# Amplifier.net
KiCad netlist of a schematic drawn in Altium Designer
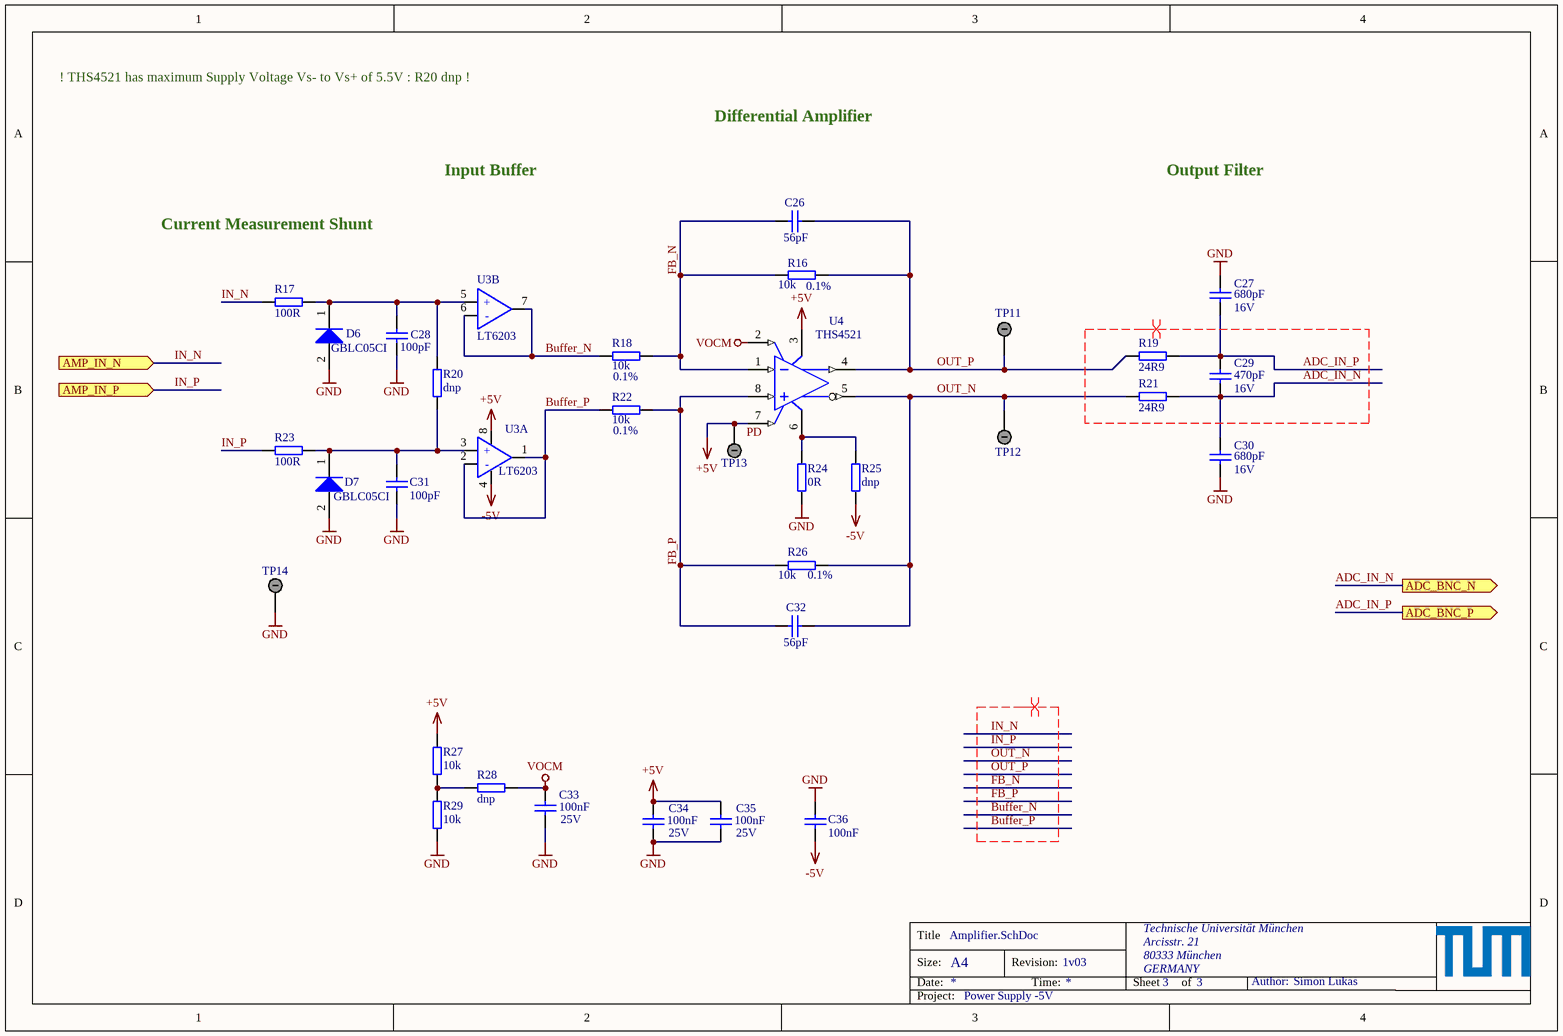
[diagram p0: Amplifier.SchDoc]

(export (version "E")
  (design (tool "Eeschema 10.0.6"))
  (components
    (comp (ref "C26")
      (value "56pF")
      (footprint "CAPC1608X07N")
      (fields
        (field (name "MF") "Vishay")
        (field (name "MPN") "VJ0603A560JXACW1BC")
        (field (name "VOLTAGE") "50V")
      )
      (libsource (lib "neg5V") (part "Cap_0603"))
    )
    (comp (ref "C27")
      (value "680pF")
      (footprint "CAPC1608X07N")
      (fields
        (field (name "MF") "Vishay")
        (field (name "MPN") "VJ0603A681GXJCW1BC")
        (field (name "VOLTAGE") "16V")
      )
      (libsource (lib "neg5V") (part "Cap_0603"))
    )
    (comp (ref "C28")
      (value "100pF")
      (footprint "CAPC1608X07N")
      (fields
        (field (name "MF") "Würth Elektronik")
        (field (name "MPN") "885012006057")
        (field (name "VOLTAGE") "50V")
      )
      (libsource (lib "neg5V") (part "Cap_0603"))
    )
    (comp (ref "C29")
      (value "470pF")
      (footprint "CAPC1608X07N")
      (fields
        (field (name "MF") "Vishay")
        (field (name "MPN") "VJ0603A471JXJCW1BC")
        (field (name "VOLTAGE") "16V")
      )
      (libsource (lib "neg5V") (part "Cap_0603"))
    )
    (comp (ref "C30")
      (value "680pF")
      (footprint "CAPC1608X07N")
      (fields
        (field (name "MF") "Vishay")
        (field (name "MPN") "VJ0603A681GXJCW1BC")
        (field (name "VOLTAGE") "16V")
      )
      (libsource (lib "neg5V") (part "Cap_0603"))
    )
    (comp (ref "C31")
      (value "100pF")
      (footprint "CAPC1608X07N")
      (fields
        (field (name "MF") "Würth Elektronik")
        (field (name "MPN") "885012006057")
        (field (name "VOLTAGE") "50V")
      )
      (libsource (lib "neg5V") (part "Cap_0603"))
    )
    (comp (ref "C32")
      (value "56pF")
      (footprint "CAPC1608X07N")
      (fields
        (field (name "MF") "Vishay")
        (field (name "MPN") "VJ0603A560JXACW1BC")
        (field (name "VOLTAGE") "50V")
      )
      (libsource (lib "neg5V") (part "Cap_0603"))
    )
    (comp (ref "C33")
      (value "100nF")
      (footprint "CAPC1608X07N")
      (fields
        (field (name "MF") "Würth Elektronik")
        (field (name "MPN") "885012206071")
        (field (name "VOLTAGE") "25V")
      )
      (libsource (lib "neg5V") (part "Cap_0603"))
    )
    (comp (ref "C34")
      (value "100nF")
      (footprint "CAPC1608X07N")
      (fields
        (field (name "MF") "Würth Elektronik")
        (field (name "MPN") "885012206071")
        (field (name "VOLTAGE") "25V")
      )
      (libsource (lib "neg5V") (part "Cap_0603"))
    )
    (comp (ref "C35")
      (value "100nF")
      (footprint "CAPC1608X07N")
      (fields
        (field (name "MF") "Würth Elektronik")
        (field (name "MPN") "885012206071")
        (field (name "VOLTAGE") "25V")
      )
      (libsource (lib "neg5V") (part "Cap_0603"))
    )
    (comp (ref "C36")
      (value "100nF")
      (footprint "CAPC1608X07N")
      (fields
        (field (name "MF") "Würth Elektronik")
        (field (name "MPN") "885012206071")
        (field (name "VOLTAGE") "25V")
      )
      (libsource (lib "neg5V") (part "Cap_0603"))
    )
    (comp (ref "D6")
      (value "GBLC05CI")
      (footprint "SOD-323_SuppressorDiode")
      (description "Ultra Low Capacitance TVS Array")
      (fields (field (name "MF") "ProTek Devices") (field (name "MPN") "GBLC05CI-LF-T7"))
      (libsource (lib "neg5V") (part "GBLCxx"))
    )
    (comp (ref "D7")
      (value "GBLC05CI")
      (footprint "SOD-323_SuppressorDiode")
      (description "Ultra Low Capacitance TVS Array")
      (fields (field (name "MF") "ProTek Devices") (field (name "MPN") "GBLC05CI-LF-T7"))
      (libsource (lib "neg5V") (part "GBLCxx"))
    )
    (comp (ref "R16")
      (value "10k")
      (footprint "RESC1608X06N")
      (fields
        (field (name "MF") "Yageo")
        (field (name "MPN") "RE0603BRE0710KL")
        (field (name "TOLERANCE") "0.1%")
      )
      (libsource (lib "neg5V") (part "R_0603"))
    )
    (comp (ref "R17")
      (value "100R")
      (footprint "RESC1608X06N")
      (fields
        (field (name "MF") "Yageo")
        (field (name "MPN") "AC0603FR-13100RL")
        (field (name "TOLERANCE") "1%")
      )
      (libsource (lib "neg5V") (part "R_0603"))
    )
    (comp (ref "R18")
      (value "10k")
      (footprint "RESC1608X06N")
      (fields
        (field (name "MF") "Yageo")
        (field (name "MPN") "RE0603BRE0710KL")
        (field (name "TOLERANCE") "0.1%")
      )
      (libsource (lib "neg5V") (part "R_0603"))
    )
    (comp (ref "R19")
      (value "24R9")
      (footprint "RESC1608X06N")
      (fields (field (name "MF") "Yageo") (field (name "MPN") "RC0603FR-1324R9L"))
      (libsource (lib "neg5V") (part "R_0603"))
    )
    (comp (ref "R20")
      (value "dnp")
      (footprint "RESC3216X65N")
      (description "WID SMD 1M 5% 0,25W")
      (fields (field (name "TOLERANCE") "5%") (field (name "MF") "ARCOL/Ohmite"))
      (libsource (lib "neg5V") (part "R_1206"))
    )
    (comp (ref "R21")
      (value "24R9")
      (footprint "RESC1608X06N")
      (fields (field (name "MF") "Yageo") (field (name "MPN") "RC0603FR-1324R9L"))
      (libsource (lib "neg5V") (part "R_0603"))
    )
    (comp (ref "R22")
      (value "10k")
      (footprint "RESC1608X06N")
      (fields
        (field (name "MF") "Yageo")
        (field (name "MPN") "RE0603BRE0710KL")
        (field (name "TOLERANCE") "0.1%")
      )
      (libsource (lib "neg5V") (part "R_0603"))
    )
    (comp (ref "R23")
      (value "100R")
      (footprint "RESC1608X06N")
      (fields
        (field (name "MF") "Yageo")
        (field (name "MPN") "AC0603FR-13100RL")
        (field (name "TOLERANCE") "1%")
      )
      (libsource (lib "neg5V") (part "R_0603"))
    )
    (comp (ref "R24")
      (value "0R")
      (footprint "RESC1608X06N")
      (fields (field (name "MF") "Vishay / Dale") (field (name "MPN") "CRCW06030000Z0EBC"))
      (libsource (lib "neg5V") (part "R_0603"))
    )
    (comp (ref "R25") (value "dnp") (footprint "RESC1608X06N") (libsource (lib "neg5V") (part "R_0603")))
    (comp (ref "R26")
      (value "10k")
      (footprint "RESC1608X06N")
      (fields
        (field (name "MF") "Yageo")
        (field (name "MPN") "RE0603BRE0710KL")
        (field (name "TOLERANCE") "0.1%")
      )
      (libsource (lib "neg5V") (part "R_0603"))
    )
    (comp (ref "R27")
      (value "10k")
      (footprint "RESC1608X06N")
      (fields (field (name "MF") "Vishay / Dale") (field (name "MPN") "CRCW060310K0FKEAC"))
      (libsource (lib "neg5V") (part "R_0603"))
    )
    (comp (ref "R28") (value "dnp") (footprint "RESC1608X06N") (libsource (lib "neg5V") (part "R_0603")))
    (comp (ref "R29")
      (value "10k")
      (footprint "RESC1608X06N")
      (fields (field (name "MF") "Vishay / Dale") (field (name "MPN") "CRCW060310K0FKEAC"))
      (libsource (lib "neg5V") (part "R_0603"))
    )
    (comp (ref "TP11")
      (value "AMP+")
      (footprint "TP_5006")
      (description "Test Point;  Compact;  THM;  PC;  .350 L;  .125 OD;  Heat Resistant Nylon 46;  Black")
      (fields
        (field (name "MANUFACTURER") "Keystone Electronics")
        (field (name "MANUFACTURER PART NUMBER") "5006")
      )
      (libsource (lib "neg5V") (part "5006"))
    )
    (comp (ref "TP12")
      (value "AMP-")
      (footprint "TP_5006")
      (description "Test Point;  Compact;  THM;  PC;  .350 L;  .125 OD;  Heat Resistant Nylon 46;  Black")
      (fields
        (field (name "MANUFACTURER") "Keystone Electronics")
        (field (name "MANUFACTURER PART NUMBER") "5006")
      )
      (libsource (lib "neg5V") (part "5006"))
    )
    (comp (ref "TP13")
      (value "PD")
      (footprint "TP_5006")
      (description "Test Point;  Compact;  THM;  PC;  .350 L;  .125 OD;  Heat Resistant Nylon 46;  Black")
      (fields
        (field (name "MANUFACTURER") "Keystone Electronics")
        (field (name "MANUFACTURER PART NUMBER") "5006")
      )
      (libsource (lib "neg5V") (part "5006"))
    )
    (comp (ref "TP14")
      (value "GND")
      (footprint "TP_5006")
      (description "Test Point;  Compact;  THM;  PC;  .350 L;  .125 OD;  Heat Resistant Nylon 46;  Black")
      (fields
        (field (name "MANUFACTURER") "Keystone Electronics")
        (field (name "MANUFACTURER PART NUMBER") "5006")
      )
      (libsource (lib "neg5V") (part "5006"))
    )
    (comp (ref "U3")
      (value "LT6203")
      (footprint "MSOP8_3x3-8N")
      (description "2 Ch Low Noise, Low Power OpAmp")
      (fields
        (field (name "MF") "Analog Devices / Linear Technology")
        (field (name "MPN") "LT6203CMS8#PBF")
        (field (name "CREATED") "Kreppel_20190830")
      )
      (libsource (lib "neg5V") (part "LT6203_MSOP8"))
    )
    (comp (ref "U4")
      (value "THS4521")
      (footprint "DGK0008A_N")
      (description "IC AMP RRO NEG OUT VLP 8VSSOP (Single Channel fully differential Amplifier)")
      (fields
        (field (name "MANUFACTURER") "Texas Instruments")
        (field (name "MANUFACTURER PART NUMBER") "THS4521IDGKR")
      )
      (libsource (lib "neg5V") (part "THS4521IDGKR"))
    )
  )
  (nets
    (net (code "1") (name "+5V") (class "Default")
      (node (ref "C34") (pin "1") (pinfunction "1_1") (pintype "passive"))
      (node (ref "C35") (pin "1") (pinfunction "1_1") (pintype "passive"))
      (node (ref "R27") (pin "1") (pintype "passive"))
      (node (ref "TP13") (pin "1") (pintype "passive"))
      (node (ref "U3") (pin "8") (pintype "passive"))
      (node (ref "U4") (pin "3") (pinfunction "VS+_3") (pintype "power_in"))
      (node (ref "U4") (pin "7") (pinfunction "~{PD}_7") (pintype "input"))
    )
    (net (code "2") (name "-5V") (class "Default")
      (node (ref "C36") (pin "2") (pinfunction "2_2") (pintype "passive"))
      (node (ref "R25") (pin "1") (pintype "passive"))
      (node (ref "U3") (pin "4") (pintype "passive"))
    )
    (net (code "3") (name "/ADC_IN_N") (class "Default")
      (node (ref "C29") (pin "2") (pinfunction "2_2") (pintype "passive"))
      (node (ref "C30") (pin "1") (pinfunction "1_1") (pintype "passive"))
      (node (ref "R21") (pin "2") (pintype "passive"))
    )
    (net (code "4") (name "/ADC_IN_P") (class "Default")
      (node (ref "C27") (pin "2") (pinfunction "2_2") (pintype "passive"))
      (node (ref "C29") (pin "1") (pinfunction "1_1") (pintype "passive"))
      (node (ref "R19") (pin "2") (pintype "passive"))
    )
    (net (code "5") (name "/Buffer_N") (class "Default")
      (node (ref "R18") (pin "1") (pintype "passive"))
      (node (ref "U3") (pin "6") (pinfunction "-_6") (pintype "passive"))
      (node (ref "U3") (pin "7") (pintype "passive"))
    )
    (net (code "6") (name "/Buffer_P") (class "Default")
      (node (ref "R22") (pin "1") (pintype "passive"))
      (node (ref "U3") (pin "1") (pintype "passive"))
      (node (ref "U3") (pin "2") (pinfunction "-_2") (pintype "passive"))
    )
    (net (code "7") (name "/FB_N") (class "Default")
      (node (ref "C26") (pin "1") (pinfunction "1_1") (pintype "passive"))
      (node (ref "R16") (pin "1") (pintype "passive"))
      (node (ref "R18") (pin "2") (pintype "passive"))
      (node (ref "U4") (pin "1") (pinfunction "VIN-_1") (pintype "input"))
    )
    (net (code "8") (name "/FB_P") (class "Default")
      (node (ref "C32") (pin "1") (pinfunction "1_1") (pintype "passive"))
      (node (ref "R22") (pin "2") (pintype "passive"))
      (node (ref "R26") (pin "1") (pintype "passive"))
      (node (ref "U4") (pin "8") (pinfunction "VIN+_8") (pintype "input"))
    )
    (net (code "9") (name "/IN_N") (class "Default") (node (ref "R17") (pin "1") (pintype "passive")))
    (net (code "10") (name "/IN_P") (class "Default") (node (ref "R23") (pin "1") (pintype "passive")))
    (net (code "11") (name "/OUT_N") (class "Default")
      (node (ref "C32") (pin "2") (pinfunction "2_2") (pintype "passive"))
      (node (ref "R21") (pin "1") (pintype "passive"))
      (node (ref "R26") (pin "2") (pintype "passive"))
      (node (ref "TP12") (pin "1") (pintype "passive"))
      (node (ref "U4") (pin "5") (pinfunction "VOUT-_5") (pintype "output"))
    )
    (net (code "12") (name "/OUT_P") (class "Default")
      (node (ref "C26") (pin "2") (pinfunction "2_2") (pintype "passive"))
      (node (ref "R16") (pin "2") (pintype "passive"))
      (node (ref "R19") (pin "1") (pintype "passive"))
      (node (ref "TP11") (pin "1") (pintype "passive"))
      (node (ref "U4") (pin "4") (pinfunction "VOUT+_4") (pintype "output"))
    )
    (net (code "14") (name "GND") (class "Default")
      (node (ref "C27") (pin "1") (pinfunction "1_1") (pintype "passive"))
      (node (ref "C28") (pin "2") (pinfunction "2_2") (pintype "passive"))
      (node (ref "C30") (pin "2") (pinfunction "2_2") (pintype "passive"))
      (node (ref "C31") (pin "2") (pinfunction "2_2") (pintype "passive"))
      (node (ref "C33") (pin "2") (pinfunction "2_2") (pintype "passive"))
      (node (ref "C34") (pin "2") (pinfunction "2_2") (pintype "passive"))
      (node (ref "C35") (pin "2") (pinfunction "2_2") (pintype "passive"))
      (node (ref "C36") (pin "1") (pinfunction "1_1") (pintype "passive"))
      (node (ref "D6") (pin "2") (pinfunction "A_2") (pintype "passive"))
      (node (ref "D7") (pin "2") (pinfunction "A_2") (pintype "passive"))
      (node (ref "R24") (pin "1") (pintype "passive"))
      (node (ref "R29") (pin "2") (pintype "passive"))
      (node (ref "TP14") (pin "1") (pintype "passive"))
    )
    (net (code "15") (name "Net-(D6-K)") (class "Default")
      (node (ref "C28") (pin "1") (pinfunction "1_1") (pintype "passive"))
      (node (ref "D6") (pin "1") (pinfunction "K_1") (pintype "passive"))
      (node (ref "R17") (pin "2") (pintype "passive"))
      (node (ref "R20") (pin "2") (pinfunction "2_2") (pintype "passive"))
      (node (ref "U3") (pin "5") (pinfunction "+_5") (pintype "passive"))
    )
    (net (code "16") (name "Net-(D7-K)") (class "Default")
      (node (ref "C31") (pin "1") (pinfunction "1_1") (pintype "passive"))
      (node (ref "D7") (pin "1") (pinfunction "K_1") (pintype "passive"))
      (node (ref "R20") (pin "1") (pinfunction "1_1") (pintype "passive"))
      (node (ref "R23") (pin "2") (pintype "passive"))
      (node (ref "U3") (pin "3") (pinfunction "+_3") (pintype "passive"))
    )
    (net (code "17") (name "Net-(R27-Pad2)") (class "Default")
      (node (ref "R27") (pin "2") (pintype "passive"))
      (node (ref "R28") (pin "2") (pintype "passive"))
      (node (ref "R29") (pin "1") (pintype "passive"))
    )
    (net (code "18") (name "Net-(U4-VS-)") (class "Default")
      (node (ref "R24") (pin "2") (pintype "passive"))
      (node (ref "R25") (pin "2") (pintype "passive"))
      (node (ref "U4") (pin "6") (pinfunction "VS-_6") (pintype "power_in"))
    )
    (net (code "19") (name "VOCM") (class "Default")
      (node (ref "C33") (pin "1") (pinfunction "1_1") (pintype "passive"))
      (node (ref "R28") (pin "1") (pintype "passive"))
      (node (ref "U4") (pin "2") (pinfunction "VOCM_2") (pintype "input"))
    )
  )
)
